# PMU.net
KiCad netlist of a schematic drawn in Altium Designer
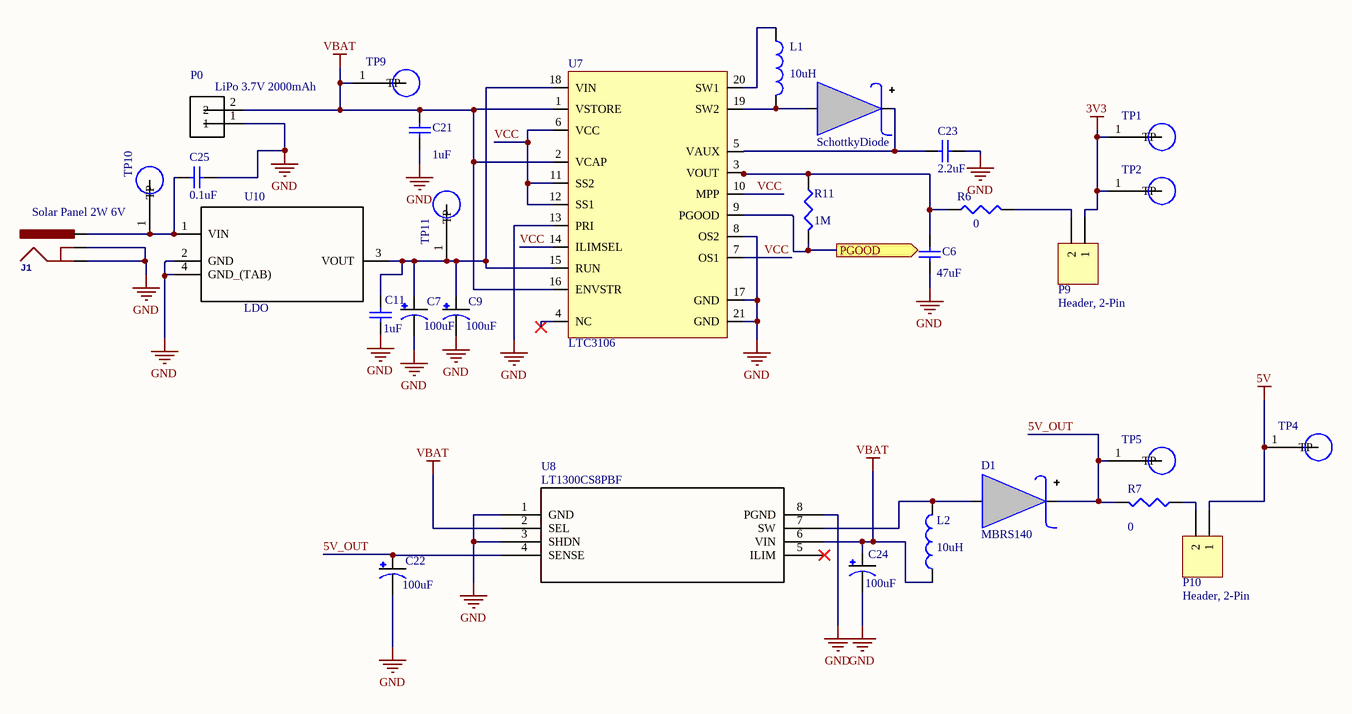
[diagram p0: PMU.SchDoc]

(export (version "E")
  (design (tool "Eeschema 10.0.6"))
  (components
    (comp (ref "C6")
      (value "47uF")
      (footprint "1608[0603]")
      (description "Capacitor (Semiconductor SIM Model)")
      (fields (field (name "PUBLISHER") "Altium Limited"))
      (libsource (lib "Miscellaneous Devices") (part "Cap Semi"))
    )
    (comp (ref "C7")
      (value "100uF")
      (footprint "CAPAE1050X1050N")
      (description "146 CTI Series 50 V 100 uF 10 x 10 x 10 mm SMT CAN Electrolytic Capacitor")
      (fields (field (name "MF") "Vishay") (field (name "MP") "MAL214699103E3"))
      (libsource (lib "LowPower_3ER_Parts") (part "MAL214699103E3"))
    )
    (comp (ref "C9")
      (value "100uF")
      (footprint "CAPAE1050X1050N")
      (description "146 CTI Series 50 V 100 uF 10 x 10 x 10 mm SMT CAN Electrolytic Capacitor")
      (fields (field (name "MF") "Vishay") (field (name "MP") "MAL214699103E3"))
      (libsource (lib "LowPower_3ER_Parts") (part "MAL214699103E3"))
    )
    (comp (ref "C11")
      (value "1uF")
      (footprint "1608[0603]")
      (description "Capacitor (Semiconductor SIM Model)")
      (fields (field (name "PUBLISHER") "Altium Limited"))
      (libsource (lib "Miscellaneous Devices") (part "Cap Semi"))
    )
    (comp (ref "C21")
      (value "1uF")
      (footprint "1608[0603]")
      (description "Capacitor (Semiconductor SIM Model)")
      (fields (field (name "PUBLISHER") "Altium Limited"))
      (libsource (lib "Miscellaneous Devices") (part "Cap Semi"))
    )
    (comp (ref "C22")
      (value "100uF")
      (footprint "CAPAE1050X1050N")
      (description "146 CTI Series 50 V 100 uF 10 x 10 x 10 mm SMT CAN Electrolytic Capacitor")
      (fields (field (name "MF") "Vishay") (field (name "MP") "MAL214699103E3"))
      (libsource (lib "LowPower_3ER_Parts") (part "MAL214699103E3"))
    )
    (comp (ref "C23")
      (value "2.2uF")
      (footprint "1608[0603]")
      (description "Capacitor (Semiconductor SIM Model)")
      (fields (field (name "PUBLISHER") "Altium Limited"))
      (libsource (lib "Miscellaneous Devices") (part "Cap Semi"))
    )
    (comp (ref "C24")
      (value "100uF")
      (footprint "CAPAE1050X1050N")
      (description "146 CTI Series 50 V 100 uF 10 x 10 x 10 mm SMT CAN Electrolytic Capacitor")
      (fields (field (name "MF") "Vishay") (field (name "MP") "MAL214699103E3"))
      (libsource (lib "LowPower_3ER_Parts") (part "MAL214699103E3"))
    )
    (comp (ref "C25")
      (value "0.1uF")
      (footprint "1608[0603]")
      (description "Capacitor (Semiconductor SIM Model)")
      (fields (field (name "PUBLISHER") "Altium Limited"))
      (libsource (lib "Miscellaneous Devices") (part "Cap Semi"))
    )
    (comp (ref "D1")
      (value "MBRS140")
      (footprint "DO-214AC")
      (libsource (lib "LowPower_3ER_Parts") (part "MBRS140"))
    )
    (comp (ref "J1")
      (value "Power Jack")
      (footprint "POWER_JACK_SMD")
      (libsource (lib "SparkFun-Connectors") (part "POWER_JACKSMD"))
    )
    (comp (ref "L1")
      (value "10uH")
      (footprint "INDM7366X500")
      (description "Inductor")
      (fields (field (name "PUBLISHER") "Altium Limited"))
      (libsource (lib "Miscellaneous Devices") (part "Inductor"))
    )
    (comp (ref "L2")
      (value "10uH")
      (footprint "INDM7366X500")
      (description "Inductor")
      (fields (field (name "PUBLISHER") "Altium Limited"))
      (libsource (lib "Miscellaneous Devices") (part "Inductor"))
    )
    (comp (ref "P0")
      (value "Battery Connector")
      (footprint "JST_B2B-PH-SM4-TB")
      (fields (field (name "MP") "B2B-PH-SM4-TB") (field (name "MF") "JST"))
      (libsource (lib "LowPower_3ER_Parts") (part "B2B-PH-SM4-TB"))
    )
    (comp (ref "P9")
      (value "Header, 2-Pin")
      (footprint "HDR1X2")
      (fields (field (name "PUBLISHER") "Altium Limited"))
      (libsource (lib "Miscellaneous Connectors") (part "Header 2"))
    )
    (comp (ref "P10")
      (value "Header, 2-Pin")
      (footprint "HDR1X2")
      (fields (field (name "PUBLISHER") "Altium Limited"))
      (libsource (lib "Miscellaneous Connectors") (part "Header 2"))
    )
    (comp (ref "R6")
      (value "0")
      (footprint "J1-0603")
      (description "Resistor")
      (fields (field (name "PUBLISHER") "Altium Limited"))
      (libsource (lib "Miscellaneous Devices") (part "Res3"))
    )
    (comp (ref "R7")
      (value "0")
      (footprint "J1-0603")
      (description "Resistor")
      (fields (field (name "PUBLISHER") "Altium Limited"))
      (libsource (lib "Miscellaneous Devices") (part "Res3"))
    )
    (comp (ref "R11")
      (value "1M")
      (footprint "J1-0603")
      (description "Resistor")
      (fields (field (name "PUBLISHER") "Altium Limited"))
      (libsource (lib "Miscellaneous Devices") (part "Res3"))
    )
    (comp (ref "SchottkyDiode")
      (value "SOD2513X120N")
      (footprint "SOD2513X120N")
      (libsource (lib "LowPower_3ER_Parts") (part "SOD2513X120N"))
    )
    (comp (ref "TP1")
      (value "Test Points")
      (footprint "TP380X203")
      (description "Phosphor Bronze Contact Miniature Silver Plated Surface Mount Test Points")
      (fields (field (name "MF") "Keystone") (field (name "DIGI-KEY_PART_NUMBER") "36-5019CT-ND"))
      (libsource (lib "LowPower_3ER_Parts") (part "5019"))
    )
    (comp (ref "TP2")
      (value "Test Points")
      (footprint "TP380X203")
      (description "Phosphor Bronze Contact Miniature Silver Plated Surface Mount Test Points")
      (fields (field (name "MF") "Keystone") (field (name "DIGI-KEY_PART_NUMBER") "36-5019CT-ND"))
      (libsource (lib "LowPower_3ER_Parts") (part "5019"))
    )
    (comp (ref "TP4")
      (value "Test Points")
      (footprint "TP380X203")
      (description "Phosphor Bronze Contact Miniature Silver Plated Surface Mount Test Points")
      (fields (field (name "MF") "Keystone") (field (name "DIGI-KEY_PART_NUMBER") "36-5019CT-ND"))
      (libsource (lib "LowPower_3ER_Parts") (part "5019"))
    )
    (comp (ref "TP5")
      (value "Test Points")
      (footprint "TP380X203")
      (description "Phosphor Bronze Contact Miniature Silver Plated Surface Mount Test Points")
      (fields (field (name "MF") "Keystone") (field (name "DIGI-KEY_PART_NUMBER") "36-5019CT-ND"))
      (libsource (lib "LowPower_3ER_Parts") (part "5019"))
    )
    (comp (ref "TP9")
      (value "Test Points")
      (footprint "TP380X203")
      (description "Phosphor Bronze Contact Miniature Silver Plated Surface Mount Test Points")
      (fields (field (name "MF") "Keystone") (field (name "DIGI-KEY_PART_NUMBER") "36-5019CT-ND"))
      (libsource (lib "LowPower_3ER_Parts") (part "5019"))
    )
    (comp (ref "TP10")
      (value "Test Points")
      (footprint "TP380X203")
      (description "Phosphor Bronze Contact Miniature Silver Plated Surface Mount Test Points")
      (fields (field (name "MF") "Keystone") (field (name "DIGI-KEY_PART_NUMBER") "36-5019CT-ND"))
      (libsource (lib "LowPower_3ER_Parts") (part "5019"))
    )
    (comp (ref "TP11")
      (value "Test Points")
      (footprint "TP380X203")
      (description "Phosphor Bronze Contact Miniature Silver Plated Surface Mount Test Points")
      (fields (field (name "MF") "Keystone") (field (name "DIGI-KEY_PART_NUMBER") "36-5019CT-ND"))
      (libsource (lib "LowPower_3ER_Parts") (part "5019"))
    )
    (comp (ref "U7")
      (value "LTC3106")
      (footprint "LTC3106")
      (libsource (lib "LowPower_3ER_Parts") (part "LTC3106"))
    )
    (comp (ref "U8")
      (value "LT1300CS8PBF")
      (footprint "SOIC-8_S")
      (fields (field (name "MP") "LT1300CS8#PBF") (field (name "MF") "Linear Technology"))
      (libsource (lib "LowPower_3ER_Parts") (part "LT1300CS8PBF"))
    )
    (comp (ref "U10")
      (value "LDO")
      (footprint "SOT230P700X180-4N")
      (description "LDO Regulator Pos 5V 0.5A Automotive 4-Pin(3+Tab) SOT-223 T/R")
      (fields (field (name "MF") "Texas Instruments") (field (name "MP") "LM2937IMPX-5.0/NOPB"))
      (libsource (lib "LowPower_3ER_Parts") (part "LM2937IMPX-5.0/NOPB"))
    )
  )
  (nets
    (net (code "1") (name "/5V_OUT") (class "Default")
      (node (ref "C22") (pin "1") (pinfunction "POS_1") (pintype "passive"))
      (node (ref "D1") (pin "2") (pinfunction "2_2") (pintype "passive"))
      (node (ref "R7") (pin "2") (pinfunction "2_2") (pintype "passive"))
      (node (ref "TP5") (pin "1") (pinfunction "TP_1") (pintype "passive"))
      (node (ref "U8") (pin "4") (pinfunction "SENSE_4") (pintype "passive"))
    )
    (net (code "2") (name "/PGOOD") (class "Default")
      (node (ref "R11") (pin "2") (pinfunction "2_2") (pintype "passive"))
      (node (ref "U7") (pin "9") (pinfunction "PGOOD_9") (pintype "passive"))
    )
    (net (code "3") (name "/VCC") (class "Default")
      (node (ref "U7") (pin "10") (pinfunction "MPP_10") (pintype "passive"))
      (node (ref "U7") (pin "11") (pinfunction "SS2_11") (pintype "passive"))
      (node (ref "U7") (pin "12") (pinfunction "SS1_12") (pintype "passive"))
      (node (ref "U7") (pin "14") (pinfunction "ILIMSEL_14") (pintype "passive"))
      (node (ref "U7") (pin "6") (pinfunction "VCC_6") (pintype "power_in"))
      (node (ref "U7") (pin "7") (pinfunction "OS1_7") (pintype "passive"))
    )
    (net (code "4") (name "3V3") (class "Default")
      (node (ref "P9") (pin "1") (pinfunction "1_1") (pintype "passive"))
      (node (ref "TP1") (pin "1") (pinfunction "TP_1") (pintype "passive"))
      (node (ref "TP2") (pin "1") (pinfunction "TP_1") (pintype "passive"))
    )
    (net (code "5") (name "5V") (class "Default")
      (node (ref "P10") (pin "1") (pinfunction "1_1") (pintype "passive"))
      (node (ref "TP4") (pin "1") (pinfunction "TP_1") (pintype "passive"))
    )
    (net (code "6") (name "GND") (class "Default")
      (node (ref "C11") (pin "1") (pinfunction "1_1") (pintype "passive"))
      (node (ref "C21") (pin "1") (pinfunction "1_1") (pintype "passive"))
      (node (ref "C22") (pin "2") (pinfunction "NEG_2") (pintype "passive"))
      (node (ref "C23") (pin "1") (pinfunction "1_1") (pintype "passive"))
      (node (ref "C24") (pin "2") (pinfunction "NEG_2") (pintype "passive"))
      (node (ref "C25") (pin "1") (pinfunction "1_1") (pintype "passive"))
      (node (ref "C6") (pin "1") (pinfunction "1_1") (pintype "passive"))
      (node (ref "C7") (pin "2") (pinfunction "NEG_2") (pintype "passive"))
      (node (ref "C9") (pin "2") (pinfunction "NEG_2") (pintype "passive"))
      (node (ref "J1") (pin "GND") (pinfunction "GNDBREAK_GND") (pintype "passive"))
      (node (ref "J1") (pin "P$4") (pinfunction "GND_P$4") (pintype "passive"))
      (node (ref "P0") (pin "1") (pinfunction "1_1") (pintype "passive"))
      (node (ref "U10") (pin "2") (pinfunction "GND_2") (pintype "passive"))
      (node (ref "U10") (pin "4") (pinfunction "GND_(TAB)_4") (pintype "passive"))
      (node (ref "U7") (pin "13") (pinfunction "PRI_13") (pintype "passive"))
      (node (ref "U7") (pin "17") (pinfunction "GND_17") (pintype "power_in"))
      (node (ref "U7") (pin "21") (pinfunction "GND_21") (pintype "power_in"))
      (node (ref "U7") (pin "8") (pinfunction "OS2_8") (pintype "passive"))
      (node (ref "U8") (pin "1") (pinfunction "GND_1") (pintype "power_in"))
      (node (ref "U8") (pin "3") (pinfunction "SHDN_3") (pintype "passive"))
      (node (ref "U8") (pin "8") (pinfunction "PGND_8") (pintype "power_in"))
    )
    (net (code "7") (name "Net-(C7-POS)") (class "Default")
      (node (ref "C11") (pin "2") (pinfunction "2_2") (pintype "passive"))
      (node (ref "C7") (pin "1") (pinfunction "POS_1") (pintype "passive"))
      (node (ref "C9") (pin "1") (pinfunction "POS_1") (pintype "passive"))
      (node (ref "TP11") (pin "1") (pinfunction "TP_1") (pintype "passive"))
      (node (ref "U10") (pin "3") (pinfunction "VOUT_3") (pintype "passive"))
      (node (ref "U7") (pin "15") (pinfunction "RUN_15") (pintype "passive"))
      (node (ref "U7") (pin "18") (pinfunction "VIN_18") (pintype "power_in"))
    )
    (net (code "8") (name "Net-(J1-PWR)") (class "Default")
      (node (ref "C25") (pin "2") (pinfunction "2_2") (pintype "passive"))
      (node (ref "J1") (pin "VIN0") (pinfunction "PWR_VIN0") (pintype "passive"))
      (node (ref "TP10") (pin "1") (pinfunction "TP_1") (pintype "passive"))
      (node (ref "U10") (pin "1") (pinfunction "VIN_1") (pintype "passive"))
    )
    (net (code "9") (name "Net-(P9-Pad2)") (class "Default")
      (node (ref "P9") (pin "2") (pinfunction "2_2") (pintype "passive"))
      (node (ref "R6") (pin "2") (pinfunction "2_2") (pintype "passive"))
    )
    (net (code "10") (name "Net-(P10-Pad2)") (class "Default")
      (node (ref "P10") (pin "2") (pinfunction "2_2") (pintype "passive"))
      (node (ref "R7") (pin "1") (pinfunction "1_1") (pintype "passive"))
    )
    (net (code "11") (name "Net-(U7-SW1)") (class "Default")
      (node (ref "L1") (pin "1") (pinfunction "1_1") (pintype "passive"))
      (node (ref "U7") (pin "20") (pinfunction "SW1_20") (pintype "passive"))
    )
    (net (code "12") (name "Net-(U7-SW2)") (class "Default")
      (node (ref "L1") (pin "2") (pinfunction "2_2") (pintype "passive"))
      (node (ref "SchottkyDiode") (pin "1") (pinfunction "1_1") (pintype "passive"))
      (node (ref "U7") (pin "19") (pinfunction "SW2_19") (pintype "passive"))
    )
    (net (code "13") (name "Net-(U7-VAUX)") (class "Default")
      (node (ref "C23") (pin "2") (pinfunction "2_2") (pintype "passive"))
      (node (ref "SchottkyDiode") (pin "2") (pinfunction "2_2") (pintype "passive"))
      (node (ref "U7") (pin "5") (pinfunction "VAUX_5") (pintype "passive"))
    )
    (net (code "14") (name "Net-(U7-VOUT)") (class "Default")
      (node (ref "C6") (pin "2") (pinfunction "2_2") (pintype "passive"))
      (node (ref "R11") (pin "1") (pinfunction "1_1") (pintype "passive"))
      (node (ref "R6") (pin "1") (pinfunction "1_1") (pintype "passive"))
      (node (ref "U7") (pin "3") (pinfunction "VOUT_3") (pintype "passive"))
    )
    (net (code "15") (name "Net-(U8-SW)") (class "Default")
      (node (ref "D1") (pin "1") (pinfunction "1_1") (pintype "passive"))
      (node (ref "L2") (pin "2") (pinfunction "2_2") (pintype "passive"))
      (node (ref "U8") (pin "7") (pinfunction "SW_7") (pintype "passive"))
    )
    (net (code "16") (name "VBAT") (class "Default")
      (node (ref "C21") (pin "2") (pinfunction "2_2") (pintype "passive"))
      (node (ref "C24") (pin "1") (pinfunction "POS_1") (pintype "passive"))
      (node (ref "L2") (pin "1") (pinfunction "1_1") (pintype "passive"))
      (node (ref "P0") (pin "2") (pinfunction "2_2") (pintype "passive"))
      (node (ref "TP9") (pin "1") (pinfunction "TP_1") (pintype "passive"))
      (node (ref "U7") (pin "1") (pinfunction "VSTORE_1") (pintype "power_in"))
      (node (ref "U7") (pin "16") (pinfunction "ENVSTR_16") (pintype "passive"))
      (node (ref "U7") (pin "2") (pinfunction "VCAP_2") (pintype "passive"))
      (node (ref "U8") (pin "2") (pinfunction "SEL_2") (pintype "passive"))
      (node (ref "U8") (pin "6") (pinfunction "VIN_6") (pintype "passive"))
    )
    (net (code "17") (name "unconnected-(U7-NC-Pad4)") (class "Default")
      (node (ref "U7") (pin "4") (pinfunction "NC_4") (pintype "passive+no_connect"))
    )
    (net (code "18") (name "unconnected-(U8-ILIM-Pad5)") (class "Default")
      (node (ref "U8") (pin "5") (pinfunction "ILIM_5") (pintype "passive+no_connect"))
    )
  )
)
